# magnetolocator.net
KiCad netlist of a schematic drawn in EAGLE
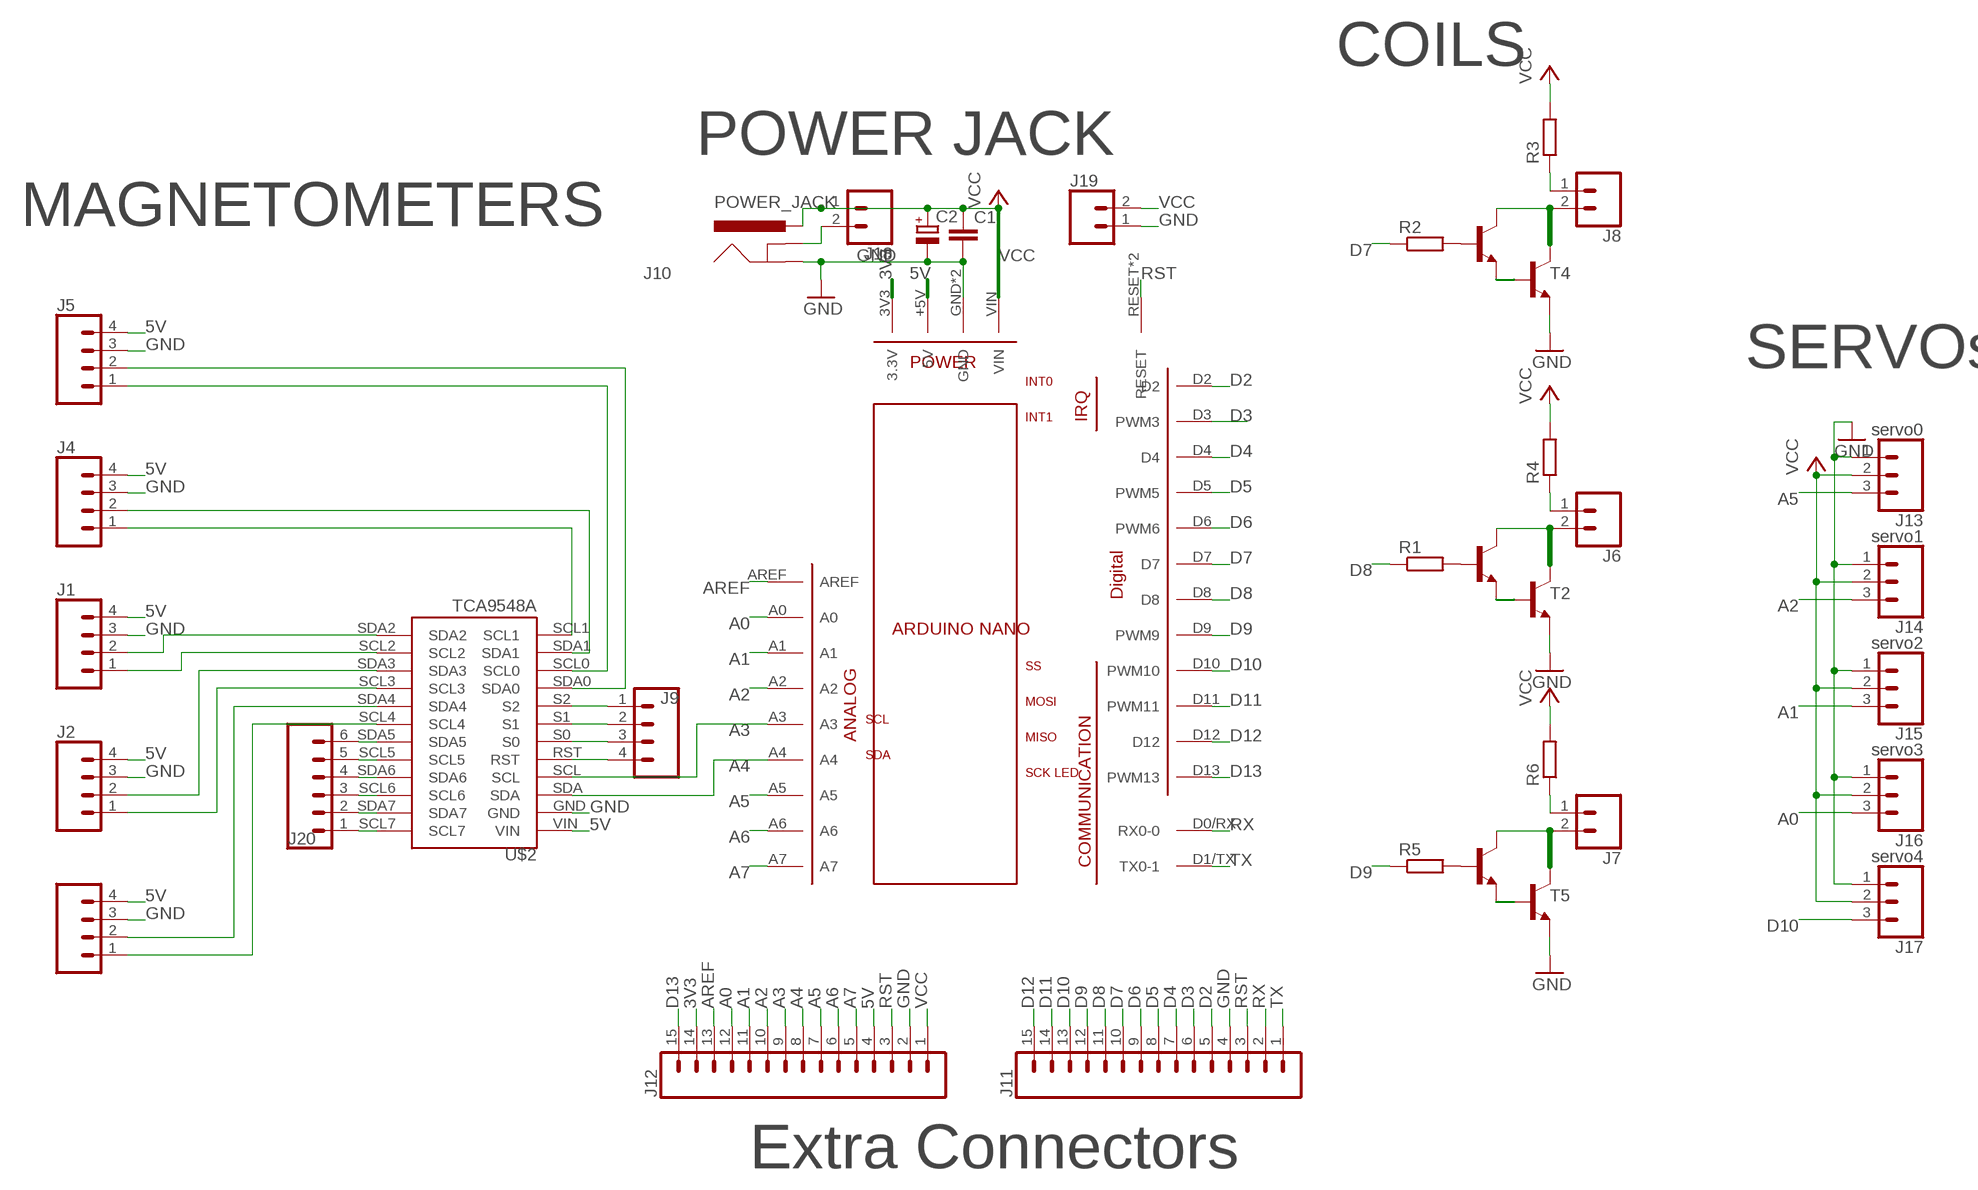
[diagram p0: schematic, sheet 1]

(export (version "E")
  (design (tool "Eeschema 10.0.6"))
  (components
    (comp (ref "C1")
      (value "C-EU025-025X050")
      (footprint "eagle-import:C025-025X050")
      (libsource (lib "eagle-import") (part "C-EU025-025X050"))
    )
    (comp (ref "C2")
      (value "CPOL-EUE2.5-5")
      (footprint "eagle-import:E2,5-5")
      (libsource (lib "eagle-import") (part "CPOL-EUE2.5-5"))
    )
    (comp (ref "J1")
      (value "CONN_04PTH")
      (footprint "eagle-import:1X04")
      (libsource (lib "eagle-import") (part "CONN_04PTH"))
    )
    (comp (ref "J2")
      (value "CONN_04PTH")
      (footprint "eagle-import:1X04")
      (libsource (lib "eagle-import") (part "CONN_04PTH"))
    )
    (comp (ref "J3")
      (value "CONN_04PTH")
      (footprint "eagle-import:1X04")
      (libsource (lib "eagle-import") (part "CONN_04PTH"))
    )
    (comp (ref "J4")
      (value "CONN_04PTH")
      (footprint "eagle-import:1X04")
      (libsource (lib "eagle-import") (part "CONN_04PTH"))
    )
    (comp (ref "J5")
      (value "CONN_04PTH")
      (footprint "eagle-import:1X04")
      (libsource (lib "eagle-import") (part "CONN_04PTH"))
    )
    (comp (ref "J6")
      (value "CONN_02")
      (footprint "eagle-import:1X02")
      (libsource (lib "eagle-import") (part "CONN_02"))
    )
    (comp (ref "J7")
      (value "CONN_02")
      (footprint "eagle-import:1X02")
      (libsource (lib "eagle-import") (part "CONN_02"))
    )
    (comp (ref "J8")
      (value "CONN_02")
      (footprint "eagle-import:1X02")
      (libsource (lib "eagle-import") (part "CONN_02"))
    )
    (comp (ref "J9")
      (value "CONN_04PTH")
      (footprint "eagle-import:1X04")
      (libsource (lib "eagle-import") (part "CONN_04PTH"))
    )
    (comp (ref "J10")
      (value "POWER_JACK")
      (footprint "eagle-import:POWER_JACK_PTH")
      (libsource (lib "eagle-import") (part "POWER_JACK"))
    )
    (comp (ref "J11")
      (value "CONN_15")
      (footprint "eagle-import:1X15")
      (libsource (lib "eagle-import") (part "CONN_15"))
    )
    (comp (ref "J12")
      (value "CONN_15")
      (footprint "eagle-import:1X15")
      (libsource (lib "eagle-import") (part "CONN_15"))
    )
    (comp (ref "J13")
      (value "servo0")
      (footprint "eagle-import:1X03")
      (libsource (lib "eagle-import") (part "CONN_03"))
    )
    (comp (ref "J14")
      (value "servo1")
      (footprint "eagle-import:1X03")
      (libsource (lib "eagle-import") (part "CONN_03"))
    )
    (comp (ref "J15")
      (value "servo2")
      (footprint "eagle-import:1X03")
      (libsource (lib "eagle-import") (part "CONN_03"))
    )
    (comp (ref "J16")
      (value "servo3")
      (footprint "eagle-import:1X03")
      (libsource (lib "eagle-import") (part "CONN_03"))
    )
    (comp (ref "J17")
      (value "servo4")
      (footprint "eagle-import:1X03")
      (libsource (lib "eagle-import") (part "CONN_03"))
    )
    (comp (ref "J18")
      (value "CONN_02")
      (footprint "eagle-import:1X02")
      (libsource (lib "eagle-import") (part "CONN_02"))
    )
    (comp (ref "J19")
      (value "CONN_02")
      (footprint "eagle-import:1X02")
      (libsource (lib "eagle-import") (part "CONN_02"))
    )
    (comp (ref "J20")
      (value "CONN_06NO_SILK_FEMALE_PTH")
      (footprint "eagle-import:1X06_NO_SILK")
      (libsource (lib "eagle-import") (part "CONN_06NO_SILK_FEMALE_PTH"))
    )
    (comp (ref "R1")
      (value "R-EU_0207/2V")
      (footprint "eagle-import:0207_2V")
      (libsource (lib "eagle-import") (part "R-EU_0207/2V"))
    )
    (comp (ref "R2")
      (value "R-EU_0207/2V")
      (footprint "eagle-import:0207_2V")
      (libsource (lib "eagle-import") (part "R-EU_0207/2V"))
    )
    (comp (ref "R3")
      (value "R-EU_0207/2V")
      (footprint "eagle-import:0207_2V")
      (libsource (lib "eagle-import") (part "R-EU_0207/2V"))
    )
    (comp (ref "R4")
      (value "R-EU_0207/2V")
      (footprint "eagle-import:0207_2V")
      (libsource (lib "eagle-import") (part "R-EU_0207/2V"))
    )
    (comp (ref "R5")
      (value "R-EU_0207/2V")
      (footprint "eagle-import:0207_2V")
      (libsource (lib "eagle-import") (part "R-EU_0207/2V"))
    )
    (comp (ref "R6")
      (value "R-EU_0207/2V")
      (footprint "eagle-import:0207_2V")
      (libsource (lib "eagle-import") (part "R-EU_0207/2V"))
    )
    (comp (ref "T1")
      (value "2N2222-NPN-TO92-EBC")
      (footprint "eagle-import:TO92-EBC")
      (libsource (lib "eagle-import") (part "-NPN-TO92-EBC2N2222"))
    )
    (comp (ref "T2")
      (value "2N2222-NPN-TO92-EBC")
      (footprint "eagle-import:TO92-EBC")
      (libsource (lib "eagle-import") (part "-NPN-TO92-EBC2N2222"))
    )
    (comp (ref "T3")
      (value "2N2222-NPN-TO92-EBC")
      (footprint "eagle-import:TO92-EBC")
      (libsource (lib "eagle-import") (part "-NPN-TO92-EBC2N2222"))
    )
    (comp (ref "T4")
      (value "2N2222-NPN-TO92-EBC")
      (footprint "eagle-import:TO92-EBC")
      (libsource (lib "eagle-import") (part "-NPN-TO92-EBC2N2222"))
    )
    (comp (ref "T5")
      (value "2N2222-NPN-TO92-EBC")
      (footprint "eagle-import:TO92-EBC")
      (libsource (lib "eagle-import") (part "-NPN-TO92-EBC2N2222"))
    )
    (comp (ref "T6")
      (value "2N2222-NPN-TO92-EBC")
      (footprint "eagle-import:TO92-EBC")
      (libsource (lib "eagle-import") (part "-NPN-TO92-EBC2N2222"))
    )
    (comp (ref "U$1")
      (value "BOARD_ARDUINO-NANO")
      (footprint "eagle-import:BOARD_ARDUINO_NANO")
      (libsource (lib "eagle-import") (part "BOARD_ARDUINO-NANO"))
    )
    (comp (ref "U$2")
      (value "TCA9548A")
      (footprint "eagle-import:TCA9548A")
      (libsource (lib "eagle-import") (part "TCA9548A"))
    )
  )
  (nets
    (net (code "1") (name "/3V3") (class "Default")
      (node (ref "J12") (pin "14") (pinfunction "14_14") (pintype "passive"))
      (node (ref "U$1") (pin "3V3") (pinfunction "3.3V_3V3") (pintype "power_in"))
    )
    (net (code "2") (name "/5V") (class "Default")
      (node (ref "J1") (pin "4") (pinfunction "4_4") (pintype "passive"))
      (node (ref "J12") (pin "4") (pinfunction "4_4") (pintype "passive"))
      (node (ref "J2") (pin "4") (pinfunction "4_4") (pintype "passive"))
      (node (ref "J3") (pin "4") (pinfunction "4_4") (pintype "passive"))
      (node (ref "J4") (pin "4") (pinfunction "4_4") (pintype "passive"))
      (node (ref "J5") (pin "4") (pinfunction "4_4") (pintype "passive"))
      (node (ref "U$1") (pin "+5V") (pinfunction "5V_+5V") (pintype "power_in"))
      (node (ref "U$2") (pin "VIN") (pinfunction "VIN_VIN") (pintype "bidirectional"))
    )
    (net (code "3") (name "/A0") (class "Default")
      (node (ref "J12") (pin "12") (pinfunction "12_12") (pintype "passive"))
      (node (ref "J16") (pin "3") (pinfunction "3_3") (pintype "passive"))
      (node (ref "U$1") (pin "A0") (pinfunction "A0_A0") (pintype "bidirectional"))
    )
    (net (code "4") (name "/A1") (class "Default")
      (node (ref "J12") (pin "11") (pinfunction "11_11") (pintype "passive"))
      (node (ref "J15") (pin "3") (pinfunction "3_3") (pintype "passive"))
      (node (ref "U$1") (pin "A1") (pinfunction "A1_A1") (pintype "bidirectional"))
    )
    (net (code "5") (name "/A2") (class "Default")
      (node (ref "J12") (pin "10") (pinfunction "10_10") (pintype "passive"))
      (node (ref "J14") (pin "3") (pinfunction "3_3") (pintype "passive"))
      (node (ref "U$1") (pin "A2") (pinfunction "A2_A2") (pintype "bidirectional"))
    )
    (net (code "6") (name "/A3") (class "Default")
      (node (ref "J12") (pin "9") (pinfunction "9_9") (pintype "passive"))
      (node (ref "U$1") (pin "A3") (pinfunction "A3_A3") (pintype "bidirectional"))
      (node (ref "U$2") (pin "SCL") (pinfunction "SCL_SCL") (pintype "bidirectional"))
    )
    (net (code "7") (name "/A4") (class "Default")
      (node (ref "J12") (pin "8") (pinfunction "8_8") (pintype "passive"))
      (node (ref "U$1") (pin "A4") (pinfunction "A4_A4") (pintype "bidirectional"))
      (node (ref "U$2") (pin "SDA") (pinfunction "SDA_SDA") (pintype "bidirectional"))
    )
    (net (code "8") (name "/A5") (class "Default")
      (node (ref "J12") (pin "7") (pinfunction "7_7") (pintype "passive"))
      (node (ref "J13") (pin "3") (pinfunction "3_3") (pintype "passive"))
      (node (ref "U$1") (pin "A5") (pinfunction "A5_A5") (pintype "bidirectional"))
    )
    (net (code "9") (name "/A6") (class "Default")
      (node (ref "J12") (pin "6") (pinfunction "6_6") (pintype "passive"))
      (node (ref "U$1") (pin "A6") (pinfunction "A6_A6") (pintype "bidirectional"))
    )
    (net (code "10") (name "/A7") (class "Default")
      (node (ref "J12") (pin "5") (pinfunction "5_5") (pintype "passive"))
      (node (ref "U$1") (pin "A7") (pinfunction "A7_A7") (pintype "bidirectional"))
    )
    (net (code "11") (name "/AREF") (class "Default")
      (node (ref "J12") (pin "13") (pinfunction "13_13") (pintype "passive"))
      (node (ref "U$1") (pin "AREF") (pinfunction "AREF_AREF") (pintype "bidirectional"))
    )
    (net (code "12") (name "/D2") (class "Default")
      (node (ref "J11") (pin "5") (pinfunction "5_5") (pintype "passive"))
      (node (ref "U$1") (pin "D2") (pinfunction "D2_D2") (pintype "bidirectional"))
    )
    (net (code "13") (name "/D3") (class "Default")
      (node (ref "J11") (pin "6") (pinfunction "6_6") (pintype "passive"))
      (node (ref "U$1") (pin "D3") (pinfunction "PWM3_D3") (pintype "bidirectional"))
    )
    (net (code "14") (name "/D4") (class "Default")
      (node (ref "J11") (pin "7") (pinfunction "7_7") (pintype "passive"))
      (node (ref "U$1") (pin "D4") (pinfunction "D4_D4") (pintype "bidirectional"))
    )
    (net (code "15") (name "/D5") (class "Default")
      (node (ref "J11") (pin "8") (pinfunction "8_8") (pintype "passive"))
      (node (ref "U$1") (pin "D5") (pinfunction "PWM5_D5") (pintype "bidirectional"))
    )
    (net (code "16") (name "/D6") (class "Default")
      (node (ref "J11") (pin "9") (pinfunction "9_9") (pintype "passive"))
      (node (ref "U$1") (pin "D6") (pinfunction "PWM6_D6") (pintype "bidirectional"))
    )
    (net (code "17") (name "/D7") (class "Default")
      (node (ref "J11") (pin "10") (pinfunction "10_10") (pintype "passive"))
      (node (ref "R2") (pin "1") (pinfunction "1_1") (pintype "passive"))
      (node (ref "U$1") (pin "D7") (pinfunction "D7_D7") (pintype "bidirectional"))
    )
    (net (code "18") (name "/D8") (class "Default")
      (node (ref "J11") (pin "11") (pinfunction "11_11") (pintype "passive"))
      (node (ref "R1") (pin "1") (pinfunction "1_1") (pintype "passive"))
      (node (ref "U$1") (pin "D8") (pinfunction "D8_D8") (pintype "bidirectional"))
    )
    (net (code "19") (name "/D9") (class "Default")
      (node (ref "J11") (pin "12") (pinfunction "12_12") (pintype "passive"))
      (node (ref "R5") (pin "1") (pinfunction "1_1") (pintype "passive"))
      (node (ref "U$1") (pin "D9") (pinfunction "PWM9_D9") (pintype "bidirectional"))
    )
    (net (code "20") (name "/D10") (class "Default")
      (node (ref "J11") (pin "13") (pinfunction "13_13") (pintype "passive"))
      (node (ref "J17") (pin "3") (pinfunction "3_3") (pintype "passive"))
      (node (ref "U$1") (pin "D10") (pinfunction "PWM10_D10") (pintype "bidirectional"))
    )
    (net (code "21") (name "/D11") (class "Default")
      (node (ref "J11") (pin "14") (pinfunction "14_14") (pintype "passive"))
      (node (ref "U$1") (pin "D11") (pinfunction "PWM11_D11") (pintype "bidirectional"))
    )
    (net (code "22") (name "/D12") (class "Default")
      (node (ref "J11") (pin "15") (pinfunction "15_15") (pintype "passive"))
      (node (ref "U$1") (pin "D12") (pinfunction "D12_D12") (pintype "bidirectional"))
    )
    (net (code "23") (name "/D13") (class "Default")
      (node (ref "J12") (pin "15") (pinfunction "15_15") (pintype "passive"))
      (node (ref "U$1") (pin "D13") (pinfunction "PWM13_D13") (pintype "bidirectional"))
    )
    (net (code "24") (name "/RST") (class "Default")
      (node (ref "J11") (pin "3") (pinfunction "3_3") (pintype "passive"))
      (node (ref "J12") (pin "3") (pinfunction "3_3") (pintype "passive"))
      (node (ref "U$1") (pin "RESET") (pinfunction "RESET_RESET") (pintype "bidirectional"))
      (node (ref "U$1") (pin "RESET1") (pinfunction "RESET_RESET1") (pintype "bidirectional"))
    )
    (net (code "25") (name "/RX") (class "Default")
      (node (ref "J11") (pin "2") (pinfunction "2_2") (pintype "passive"))
      (node (ref "U$1") (pin "D0/RX") (pinfunction "RX0-0_D0/RX") (pintype "bidirectional"))
    )
    (net (code "26") (name "/TX") (class "Default")
      (node (ref "J11") (pin "1") (pinfunction "1_1") (pintype "passive"))
      (node (ref "U$1") (pin "D1/TX") (pinfunction "TX0-1_D1/TX") (pintype "bidirectional"))
    )
    (net (code "27") (name "GND") (class "Default")
      (node (ref "C1") (pin "2") (pinfunction "2_2") (pintype "passive"))
      (node (ref "C2") (pin "-") (pinfunction "-_-") (pintype "passive"))
      (node (ref "J1") (pin "3") (pinfunction "3_3") (pintype "passive"))
      (node (ref "J10") (pin "GND") (pinfunction "GND_GND") (pintype "bidirectional"))
      (node (ref "J11") (pin "4") (pinfunction "4_4") (pintype "passive"))
      (node (ref "J12") (pin "2") (pinfunction "2_2") (pintype "passive"))
      (node (ref "J13") (pin "1") (pinfunction "1_1") (pintype "passive"))
      (node (ref "J14") (pin "1") (pinfunction "1_1") (pintype "passive"))
      (node (ref "J15") (pin "1") (pinfunction "1_1") (pintype "passive"))
      (node (ref "J16") (pin "1") (pinfunction "1_1") (pintype "passive"))
      (node (ref "J17") (pin "1") (pinfunction "1_1") (pintype "passive"))
      (node (ref "J19") (pin "1") (pinfunction "1_1") (pintype "passive"))
      (node (ref "J2") (pin "3") (pinfunction "3_3") (pintype "passive"))
      (node (ref "J3") (pin "3") (pinfunction "3_3") (pintype "passive"))
      (node (ref "J4") (pin "3") (pinfunction "3_3") (pintype "passive"))
      (node (ref "J5") (pin "3") (pinfunction "3_3") (pintype "passive"))
      (node (ref "T2") (pin "E") (pinfunction "E_E") (pintype "passive"))
      (node (ref "T4") (pin "E") (pinfunction "E_E") (pintype "passive"))
      (node (ref "T5") (pin "E") (pinfunction "E_E") (pintype "passive"))
      (node (ref "U$1") (pin "GND") (pinfunction "GND_GND") (pintype "power_in"))
      (node (ref "U$1") (pin "GND1") (pinfunction "GND_GND1") (pintype "power_in"))
      (node (ref "U$2") (pin "GND") (pinfunction "GND_GND") (pintype "bidirectional"))
    )
    (net (code "28") (name "Net-(J1-Pad1)") (class "Default")
      (node (ref "J1") (pin "1") (pinfunction "1_1") (pintype "passive"))
      (node (ref "U$2") (pin "SCL2") (pinfunction "SCL2_SCL2") (pintype "bidirectional"))
    )
    (net (code "29") (name "Net-(J1-Pad2)") (class "Default")
      (node (ref "J1") (pin "2") (pinfunction "2_2") (pintype "passive"))
      (node (ref "U$2") (pin "SDA2") (pinfunction "SDA2_SDA2") (pintype "bidirectional"))
    )
    (net (code "30") (name "Net-(J2-Pad1)") (class "Default")
      (node (ref "J2") (pin "1") (pinfunction "1_1") (pintype "passive"))
      (node (ref "U$2") (pin "SCL3") (pinfunction "SCL3_SCL3") (pintype "bidirectional"))
    )
    (net (code "31") (name "Net-(J2-Pad2)") (class "Default")
      (node (ref "J2") (pin "2") (pinfunction "2_2") (pintype "passive"))
      (node (ref "U$2") (pin "SDA3") (pinfunction "SDA3_SDA3") (pintype "bidirectional"))
    )
    (net (code "32") (name "Net-(J3-Pad1)") (class "Default")
      (node (ref "J3") (pin "1") (pinfunction "1_1") (pintype "passive"))
      (node (ref "U$2") (pin "SCL4") (pinfunction "SCL4_SCL4") (pintype "bidirectional"))
    )
    (net (code "33") (name "Net-(J3-Pad2)") (class "Default")
      (node (ref "J3") (pin "2") (pinfunction "2_2") (pintype "passive"))
      (node (ref "U$2") (pin "SDA4") (pinfunction "SDA4_SDA4") (pintype "bidirectional"))
    )
    (net (code "34") (name "Net-(J4-Pad1)") (class "Default")
      (node (ref "J4") (pin "1") (pinfunction "1_1") (pintype "passive"))
      (node (ref "U$2") (pin "SCL1") (pinfunction "SCL1_SCL1") (pintype "bidirectional"))
    )
    (net (code "35") (name "Net-(J4-Pad2)") (class "Default")
      (node (ref "J4") (pin "2") (pinfunction "2_2") (pintype "passive"))
      (node (ref "U$2") (pin "SDA1") (pinfunction "SDA1_SDA1") (pintype "bidirectional"))
    )
    (net (code "36") (name "Net-(J5-Pad1)") (class "Default")
      (node (ref "J5") (pin "1") (pinfunction "1_1") (pintype "passive"))
      (node (ref "U$2") (pin "SCL0") (pinfunction "SCL0_SCL0") (pintype "bidirectional"))
    )
    (net (code "37") (name "Net-(J5-Pad2)") (class "Default")
      (node (ref "J5") (pin "2") (pinfunction "2_2") (pintype "passive"))
      (node (ref "U$2") (pin "SDA0") (pinfunction "SDA0_SDA0") (pintype "bidirectional"))
    )
    (net (code "38") (name "Net-(J6-Pad1)") (class "Default")
      (node (ref "J6") (pin "1") (pinfunction "1_1") (pintype "passive"))
      (node (ref "R4") (pin "1") (pinfunction "1_1") (pintype "passive"))
    )
    (net (code "39") (name "Net-(J6-Pad2)") (class "Default")
      (node (ref "J6") (pin "2") (pinfunction "2_2") (pintype "passive"))
      (node (ref "T2") (pin "C") (pinfunction "C_C") (pintype "passive"))
      (node (ref "T3") (pin "C") (pinfunction "C_C") (pintype "passive"))
    )
    (net (code "40") (name "Net-(J7-Pad1)") (class "Default")
      (node (ref "J7") (pin "1") (pinfunction "1_1") (pintype "passive"))
      (node (ref "R6") (pin "1") (pinfunction "1_1") (pintype "passive"))
    )
    (net (code "41") (name "Net-(J7-Pad2)") (class "Default")
      (node (ref "J7") (pin "2") (pinfunction "2_2") (pintype "passive"))
      (node (ref "T5") (pin "C") (pinfunction "C_C") (pintype "passive"))
      (node (ref "T6") (pin "C") (pinfunction "C_C") (pintype "passive"))
    )
    (net (code "42") (name "Net-(J8-Pad1)") (class "Default")
      (node (ref "J8") (pin "1") (pinfunction "1_1") (pintype "passive"))
      (node (ref "R3") (pin "1") (pinfunction "1_1") (pintype "passive"))
    )
    (net (code "43") (name "Net-(J8-Pad2)") (class "Default")
      (node (ref "J8") (pin "2") (pinfunction "2_2") (pintype "passive"))
      (node (ref "T1") (pin "C") (pinfunction "C_C") (pintype "passive"))
      (node (ref "T4") (pin "C") (pinfunction "C_C") (pintype "passive"))
    )
    (net (code "44") (name "Net-(J9-Pad1)") (class "Default")
      (node (ref "J9") (pin "1") (pinfunction "1_1") (pintype "passive"))
      (node (ref "U$2") (pin "S2") (pinfunction "S2_S2") (pintype "bidirectional"))
    )
    (net (code "45") (name "Net-(J9-Pad2)") (class "Default")
      (node (ref "J9") (pin "2") (pinfunction "2_2") (pintype "passive"))
      (node (ref "U$2") (pin "S1") (pinfunction "S1_S1") (pintype "bidirectional"))
    )
    (net (code "46") (name "Net-(J9-Pad3)") (class "Default")
      (node (ref "J9") (pin "3") (pinfunction "3_3") (pintype "passive"))
      (node (ref "U$2") (pin "S0") (pinfunction "S0_S0") (pintype "bidirectional"))
    )
    (net (code "47") (name "Net-(J9-Pad4)") (class "Default")
      (node (ref "J9") (pin "4") (pinfunction "4_4") (pintype "passive"))
      (node (ref "U$2") (pin "RST") (pinfunction "RST_RST") (pintype "bidirectional"))
    )
    (net (code "48") (name "Net-(J10-PadGNDBREAK)") (class "Default")
      (node (ref "J10") (pin "GNDBREAK") (pinfunction "GNDBREAK_GNDBREAK") (pintype "bidirectional"))
      (node (ref "J18") (pin "2") (pinfunction "2_2") (pintype "passive"))
    )
    (net (code "49") (name "Net-(J20-Pad1)") (class "Default")
      (node (ref "J20") (pin "1") (pinfunction "1_1") (pintype "passive"))
      (node (ref "U$2") (pin "SCL7") (pinfunction "SCL7_SCL7") (pintype "bidirectional"))
    )
    (net (code "50") (name "Net-(J20-Pad2)") (class "Default")
      (node (ref "J20") (pin "2") (pinfunction "2_2") (pintype "passive"))
      (node (ref "U$2") (pin "SDA7") (pinfunction "SDA7_SDA7") (pintype "bidirectional"))
    )
    (net (code "51") (name "Net-(J20-Pad3)") (class "Default")
      (node (ref "J20") (pin "3") (pinfunction "3_3") (pintype "passive"))
      (node (ref "U$2") (pin "SCL6") (pinfunction "SCL6_SCL6") (pintype "bidirectional"))
    )
    (net (code "52") (name "Net-(J20-Pad4)") (class "Default")
      (node (ref "J20") (pin "4") (pinfunction "4_4") (pintype "passive"))
      (node (ref "U$2") (pin "SDA6") (pinfunction "SDA6_SDA6") (pintype "bidirectional"))
    )
    (net (code "53") (name "Net-(J20-Pad5)") (class "Default")
      (node (ref "J20") (pin "5") (pinfunction "5_5") (pintype "passive"))
      (node (ref "U$2") (pin "SCL5") (pinfunction "SCL5_SCL5") (pintype "bidirectional"))
    )
    (net (code "54") (name "Net-(J20-Pad6)") (class "Default")
      (node (ref "J20") (pin "6") (pinfunction "6_6") (pintype "passive"))
      (node (ref "U$2") (pin "SDA5") (pinfunction "SDA5_SDA5") (pintype "bidirectional"))
    )
    (net (code "55") (name "Net-(R1-Pad2)") (class "Default")
      (node (ref "R1") (pin "2") (pinfunction "2_2") (pintype "passive"))
      (node (ref "T3") (pin "B") (pinfunction "B_B") (pintype "passive"))
    )
    (net (code "56") (name "Net-(R2-Pad2)") (class "Default")
      (node (ref "R2") (pin "2") (pinfunction "2_2") (pintype "passive"))
      (node (ref "T1") (pin "B") (pinfunction "B_B") (pintype "passive"))
    )
    (net (code "57") (name "Net-(R5-Pad2)") (class "Default")
      (node (ref "R5") (pin "2") (pinfunction "2_2") (pintype "passive"))
      (node (ref "T6") (pin "B") (pinfunction "B_B") (pintype "passive"))
    )
    (net (code "58") (name "Net-(T1-PadE)") (class "Default")
      (node (ref "T1") (pin "E") (pinfunction "E_E") (pintype "passive"))
      (node (ref "T4") (pin "B") (pinfunction "B_B") (pintype "passive"))
    )
    (net (code "59") (name "Net-(T2-PadB)") (class "Default")
      (node (ref "T2") (pin "B") (pinfunction "B_B") (pintype "passive"))
      (node (ref "T3") (pin "E") (pinfunction "E_E") (pintype "passive"))
    )
    (net (code "60") (name "Net-(T5-PadB)") (class "Default")
      (node (ref "T5") (pin "B") (pinfunction "B_B") (pintype "passive"))
      (node (ref "T6") (pin "E") (pinfunction "E_E") (pintype "passive"))
    )
    (net (code "61") (name "VCC") (class "Default")
      (node (ref "C1") (pin "1") (pinfunction "1_1") (pintype "passive"))
      (node (ref "C2") (pin "+") (pinfunction "+_+") (pintype "passive"))
      (node (ref "J10") (pin "PWR") (pinfunction "PWR_PWR") (pintype "bidirectional"))
      (node (ref "J12") (pin "1") (pinfunction "1_1") (pintype "passive"))
      (node (ref "J13") (pin "2") (pinfunction "2_2") (pintype "passive"))
      (node (ref "J14") (pin "2") (pinfunction "2_2") (pintype "passive"))
      (node (ref "J15") (pin "2") (pinfunction "2_2") (pintype "passive"))
      (node (ref "J16") (pin "2") (pinfunction "2_2") (pintype "passive"))
      (node (ref "J17") (pin "2") (pinfunction "2_2") (pintype "passive"))
      (node (ref "J18") (pin "1") (pinfunction "1_1") (pintype "passive"))
      (node (ref "J19") (pin "2") (pinfunction "2_2") (pintype "passive"))
      (node (ref "R3") (pin "2") (pinfunction "2_2") (pintype "passive"))
      (node (ref "R4") (pin "2") (pinfunction "2_2") (pintype "passive"))
      (node (ref "R6") (pin "2") (pinfunction "2_2") (pintype "passive"))
      (node (ref "U$1") (pin "VIN") (pinfunction "VIN_VIN") (pintype "power_in"))
    )
  )
)
